# controller-left.net
KiCad netlist of a schematic drawn in EAGLE
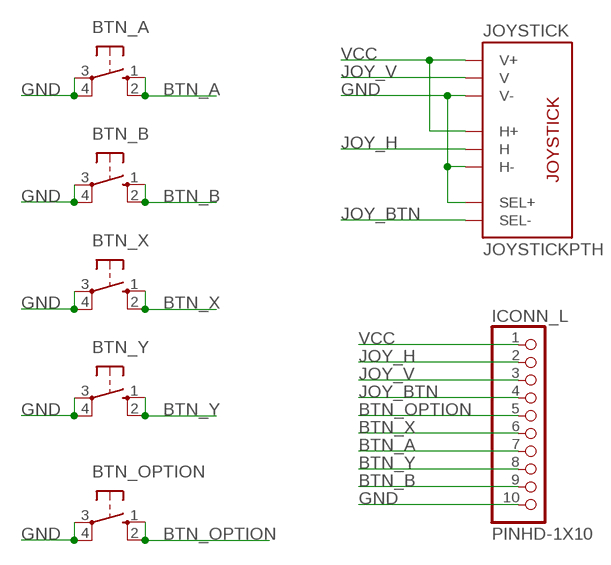
[diagram p0: schematic, sheet 1]

(export (version "E")
  (design (tool "Eeschema 10.0.6"))
  (components
    (comp (ref "BTN_A")
      (value "40-XX-ROUND")
      (footprint "eagle-import:B3F-40XX-ROUND")
      (libsource (lib "eagle-import") (part "40-XX-ROUND"))
    )
    (comp (ref "BTN_B")
      (value "40-XX-ROUND")
      (footprint "eagle-import:B3F-40XX-ROUND")
      (libsource (lib "eagle-import") (part "40-XX-ROUND"))
    )
    (comp (ref "BTN_OPTION")
      (value "40-XX-ROUND")
      (footprint "eagle-import:B3F-40XX-ROUND")
      (libsource (lib "eagle-import") (part "40-XX-ROUND"))
    )
    (comp (ref "BTN_X")
      (value "40-XX-ROUND")
      (footprint "eagle-import:B3F-40XX-ROUND")
      (libsource (lib "eagle-import") (part "40-XX-ROUND"))
    )
    (comp (ref "BTN_Y")
      (value "40-XX-ROUND")
      (footprint "eagle-import:B3F-40XX-ROUND")
      (libsource (lib "eagle-import") (part "40-XX-ROUND"))
    )
    (comp (ref "ICONN_L")
      (value "PINHD-1X10")
      (footprint "eagle-import:1X10-BIG")
      (libsource (lib "eagle-import") (part "PINHD-1X10"))
    )
    (comp (ref "JOYSTICK")
      (value "JOYSTICKPTH")
      (footprint "eagle-import:JOYSTICK")
      (libsource (lib "eagle-import") (part "JOYSTICKPTH"))
    )
  )
  (nets
    (net (code "1") (name "/BTN_A") (class "Default")
      (node (ref "BTN_A") (pin "1") (pinfunction "S_1") (pintype "passive"))
      (node (ref "BTN_A") (pin "2") (pinfunction "S1_2") (pintype "passive"))
      (node (ref "ICONN_L") (pin "7") (pinfunction "7_7") (pintype "passive"))
    )
    (net (code "2") (name "/BTN_B") (class "Default")
      (node (ref "BTN_B") (pin "1") (pinfunction "S_1") (pintype "passive"))
      (node (ref "BTN_B") (pin "2") (pinfunction "S1_2") (pintype "passive"))
      (node (ref "ICONN_L") (pin "9") (pinfunction "9_9") (pintype "passive"))
    )
    (net (code "3") (name "/BTN_OPTION") (class "Default")
      (node (ref "BTN_OPTION") (pin "1") (pinfunction "S_1") (pintype "passive"))
      (node (ref "BTN_OPTION") (pin "2") (pinfunction "S1_2") (pintype "passive"))
      (node (ref "ICONN_L") (pin "5") (pinfunction "5_5") (pintype "passive"))
    )
    (net (code "4") (name "/BTN_X") (class "Default")
      (node (ref "BTN_X") (pin "1") (pinfunction "S_1") (pintype "passive"))
      (node (ref "BTN_X") (pin "2") (pinfunction "S1_2") (pintype "passive"))
      (node (ref "ICONN_L") (pin "6") (pinfunction "6_6") (pintype "passive"))
    )
    (net (code "5") (name "/BTN_Y") (class "Default")
      (node (ref "BTN_Y") (pin "1") (pinfunction "S_1") (pintype "passive"))
      (node (ref "BTN_Y") (pin "2") (pinfunction "S1_2") (pintype "passive"))
      (node (ref "ICONN_L") (pin "8") (pinfunction "8_8") (pintype "passive"))
    )
    (net (code "6") (name "/GND") (class "Default")
      (node (ref "BTN_A") (pin "3") (pinfunction "P_3") (pintype "passive"))
      (node (ref "BTN_A") (pin "4") (pinfunction "P1_4") (pintype "passive"))
      (node (ref "BTN_B") (pin "3") (pinfunction "P_3") (pintype "passive"))
      (node (ref "BTN_B") (pin "4") (pinfunction "P1_4") (pintype "passive"))
      (node (ref "BTN_OPTION") (pin "3") (pinfunction "P_3") (pintype "passive"))
      (node (ref "BTN_OPTION") (pin "4") (pinfunction "P1_4") (pintype "passive"))
      (node (ref "BTN_X") (pin "3") (pinfunction "P_3") (pintype "passive"))
      (node (ref "BTN_X") (pin "4") (pinfunction "P1_4") (pintype "passive"))
      (node (ref "BTN_Y") (pin "3") (pinfunction "P_3") (pintype "passive"))
      (node (ref "BTN_Y") (pin "4") (pinfunction "P1_4") (pintype "passive"))
      (node (ref "ICONN_L") (pin "10") (pinfunction "10_10") (pintype "passive"))
      (node (ref "JOYSTICK") (pin "B1A") (pinfunction "SEL+_B1A") (pintype "bidirectional"))
      (node (ref "JOYSTICK") (pin "H3") (pinfunction "H-_H3") (pintype "bidirectional"))
      (node (ref "JOYSTICK") (pin "V3") (pinfunction "V-_V3") (pintype "bidirectional"))
    )
    (net (code "7") (name "/JOY_BTN") (class "Default")
      (node (ref "ICONN_L") (pin "4") (pinfunction "4_4") (pintype "passive"))
      (node (ref "JOYSTICK") (pin "B2A") (pinfunction "SEL-_B2A") (pintype "bidirectional"))
    )
    (net (code "8") (name "/JOY_H") (class "Default")
      (node (ref "ICONN_L") (pin "2") (pinfunction "2_2") (pintype "passive"))
      (node (ref "JOYSTICK") (pin "H2") (pinfunction "H_H2") (pintype "bidirectional"))
    )
    (net (code "9") (name "/JOY_V") (class "Default")
      (node (ref "ICONN_L") (pin "3") (pinfunction "3_3") (pintype "passive"))
      (node (ref "JOYSTICK") (pin "V2") (pinfunction "V_V2") (pintype "bidirectional"))
    )
    (net (code "10") (name "/VCC") (class "Default")
      (node (ref "ICONN_L") (pin "1") (pinfunction "1_1") (pintype "passive"))
      (node (ref "JOYSTICK") (pin "H1") (pinfunction "H+_H1") (pintype "bidirectional"))
      (node (ref "JOYSTICK") (pin "V1") (pinfunction "V+_V1") (pintype "bidirectional"))
    )
  )
)
